# mosfet.net
KiCad netlist of a schematic drawn in Altium Designer
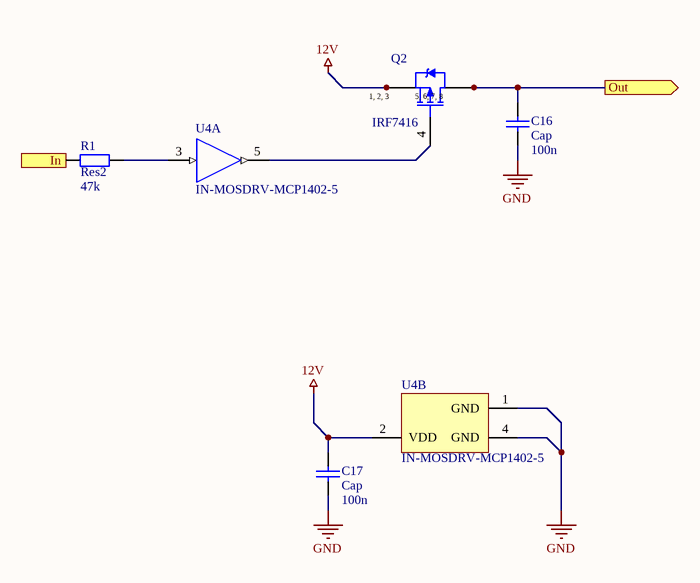
[diagram p0: mosfet.SchDoc]

(export (version "E")
  (design (tool "Eeschema 10.0.6"))
  (components
    (comp (ref "C16")
      (value "Cap")
      (footprint "SMD_Resistor_1206")
      (description "Capacitor")
      (fields (field (name "ALTIUM_VALUE") "100n") (field (name "PUBLISHER") "Altium Limited"))
      (libsource (lib "Miscellaneous Devices") (part "Cap"))
    )
    (comp (ref "C17")
      (value "Cap")
      (footprint "SMD_Resistor_1206")
      (description "Capacitor")
      (fields (field (name "ALTIUM_VALUE") "100n") (field (name "PUBLISHER") "Altium Limited"))
      (libsource (lib "Miscellaneous Devices") (part "Cap"))
    )
    (comp (ref "Q2")
      (value "IRF7416")
      (footprint "SO-8_L")
      (description "HEXFET Power MOSFET")
      (fields (field (name "PUBLISHER") "Altium Limited"))
      (libsource (lib "IR Discrete MOSFET - Power") (part "IRF7416"))
    )
    (comp (ref "R1")
      (value "Res2")
      (footprint "SMD_Resistor_1206")
      (description "Resistor")
      (fields (field (name "ALTIUM_VALUE") "47k") (field (name "PUBLISHER") "Altium Limited"))
      (libsource (lib "Miscellaneous Devices") (part "Res2"))
    )
    (comp (ref "U4")
      (value "IN-MOSDRV-MCP1402-5")
      (footprint "SOT-23-OT5_M")
      (libsource (lib "IN-MOSDRV-MCP1402-5") (part "IN-MOSDRV-MCP1402-5"))
    )
  )
  (nets
    (net (code "1") (name "/In") (class "Default")
      (node (ref "R1") (pin "1") (pinfunction "1_1") (pintype "passive"))
    )
    (net (code "2") (name "/Out") (class "Default")
      (node (ref "C16") (pin "2") (pinfunction "2_2") (pintype "passive"))
      (node (ref "Q2") (pin "5") (pinfunction "D_5") (pintype "passive"))
      (node (ref "Q2") (pin "6") (pinfunction "D_6") (pintype "passive"))
      (node (ref "Q2") (pin "7") (pinfunction "D_7") (pintype "passive"))
      (node (ref "Q2") (pin "8") (pinfunction "D_8") (pintype "passive"))
    )
    (net (code "3") (name "12V") (class "Default")
      (node (ref "C17") (pin "1") (pinfunction "1_1") (pintype "passive"))
      (node (ref "Q2") (pin "1") (pinfunction "S_1") (pintype "passive"))
      (node (ref "Q2") (pin "2") (pinfunction "S_2") (pintype "passive"))
      (node (ref "Q2") (pin "3") (pinfunction "S_3") (pintype "passive"))
      (node (ref "U4") (pin "2") (pinfunction "VDD_2") (pintype "power_in"))
    )
    (net (code "4") (name "GND") (class "Default")
      (node (ref "C16") (pin "1") (pinfunction "1_1") (pintype "passive"))
      (node (ref "C17") (pin "2") (pinfunction "2_2") (pintype "passive"))
      (node (ref "U4") (pin "1") (pinfunction "GND_1") (pintype "power_in"))
      (node (ref "U4") (pin "4") (pinfunction "GND_4") (pintype "power_in"))
    )
    (net (code "5") (name "Net-(Q2-G)") (class "Default")
      (node (ref "Q2") (pin "4") (pinfunction "G_4") (pintype "passive"))
      (node (ref "U4") (pin "5") (pinfunction "OUT_5") (pintype "output"))
    )
    (net (code "6") (name "Net-(U4A-IN)") (class "Default")
      (node (ref "R1") (pin "2") (pinfunction "2_2") (pintype "passive"))
      (node (ref "U4") (pin "3") (pinfunction "IN_3") (pintype "input"))
    )
  )
)
